# WallGrinder.net
KiCad netlist of a schematic drawn in EAGLE
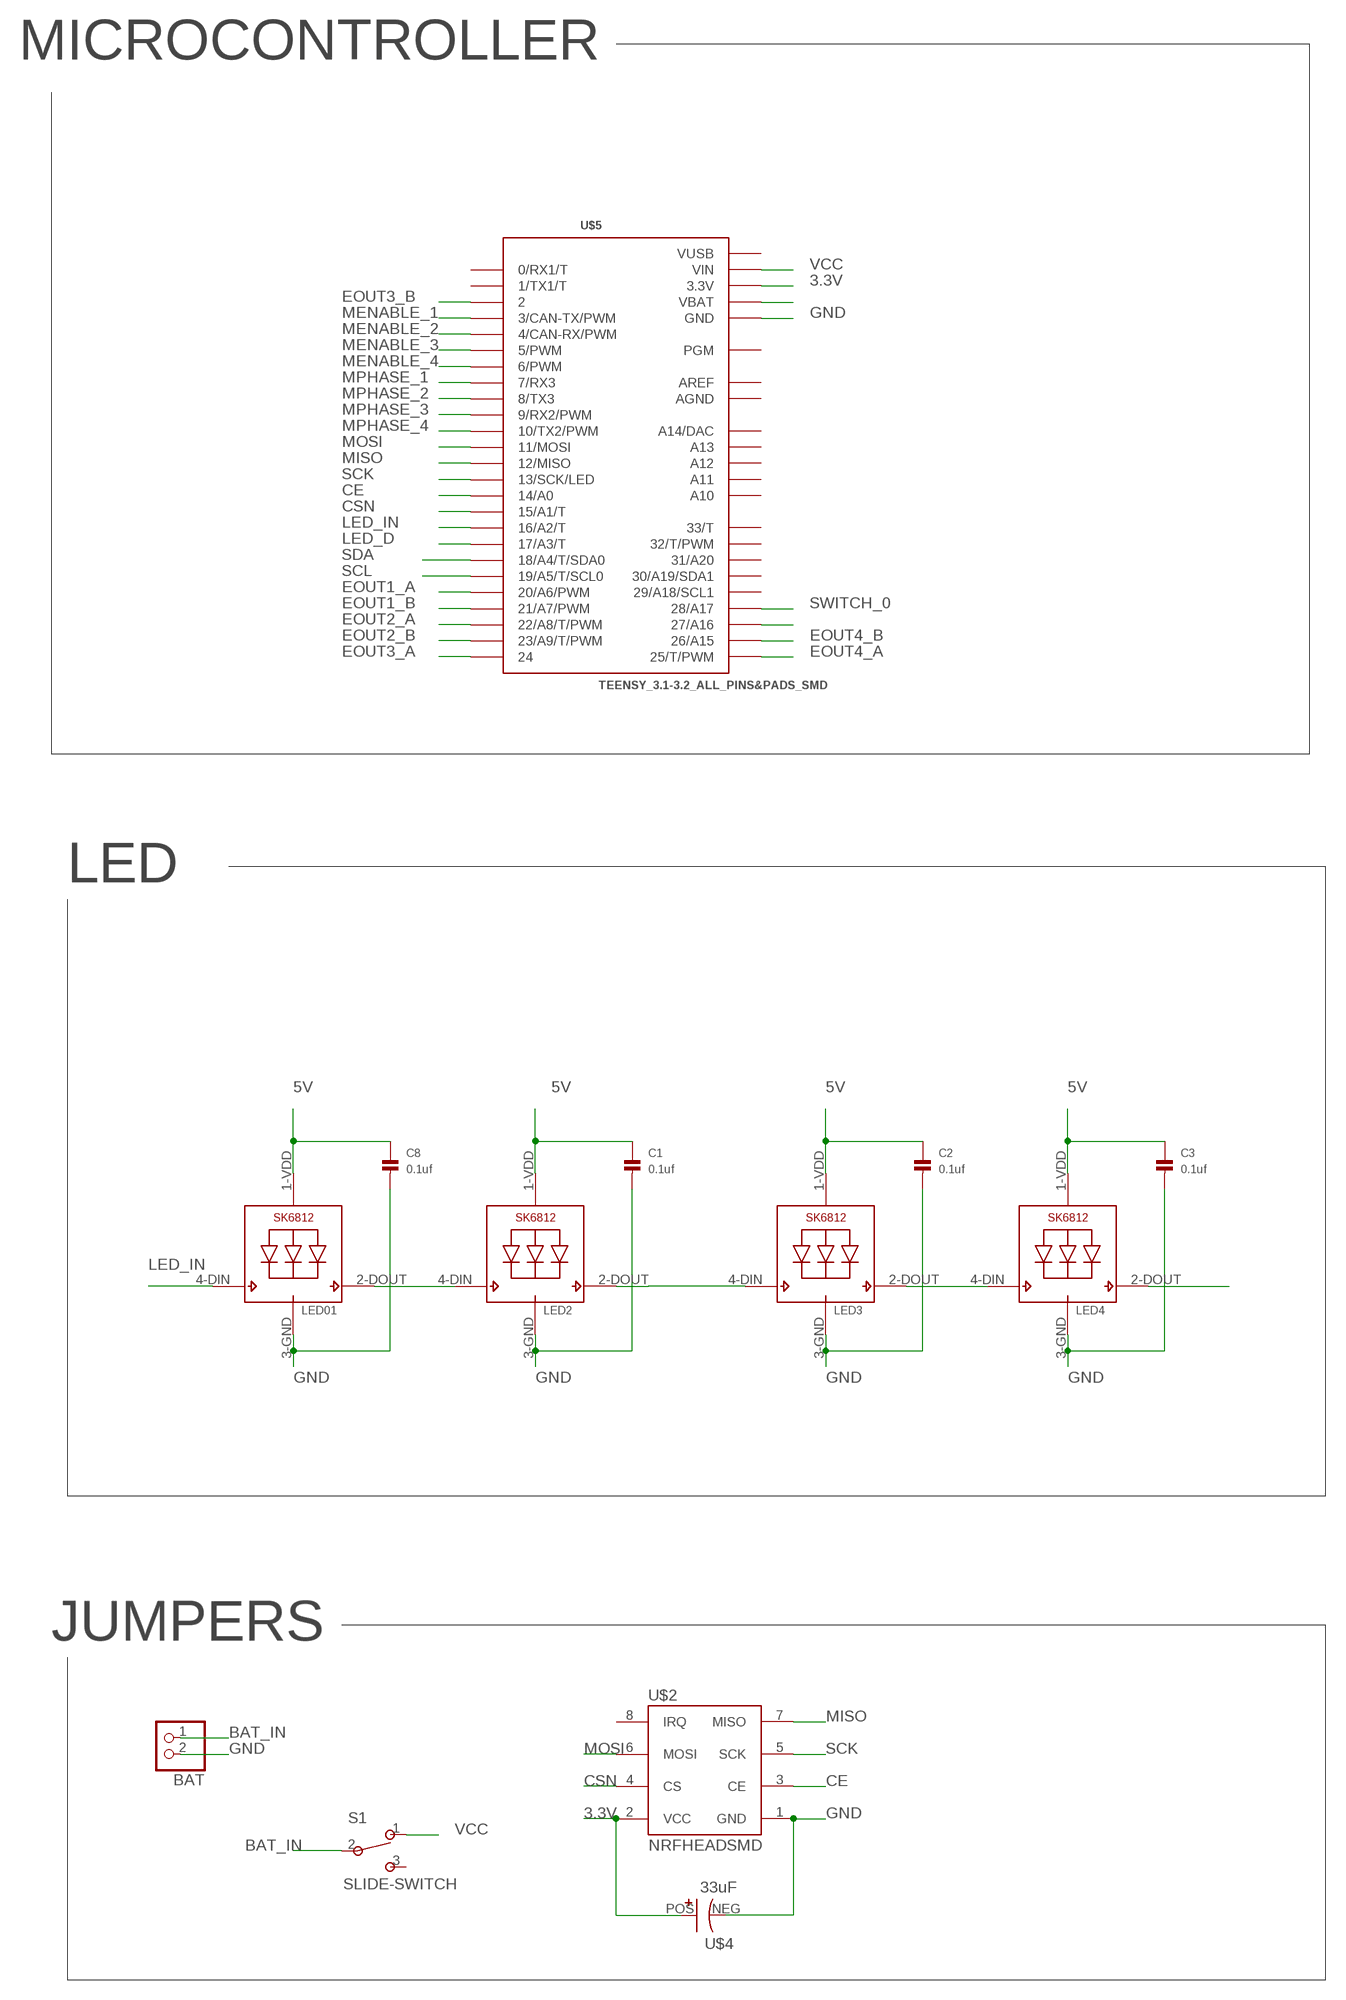
[diagram p0: schematic, sheet 1, part 1 of 2]
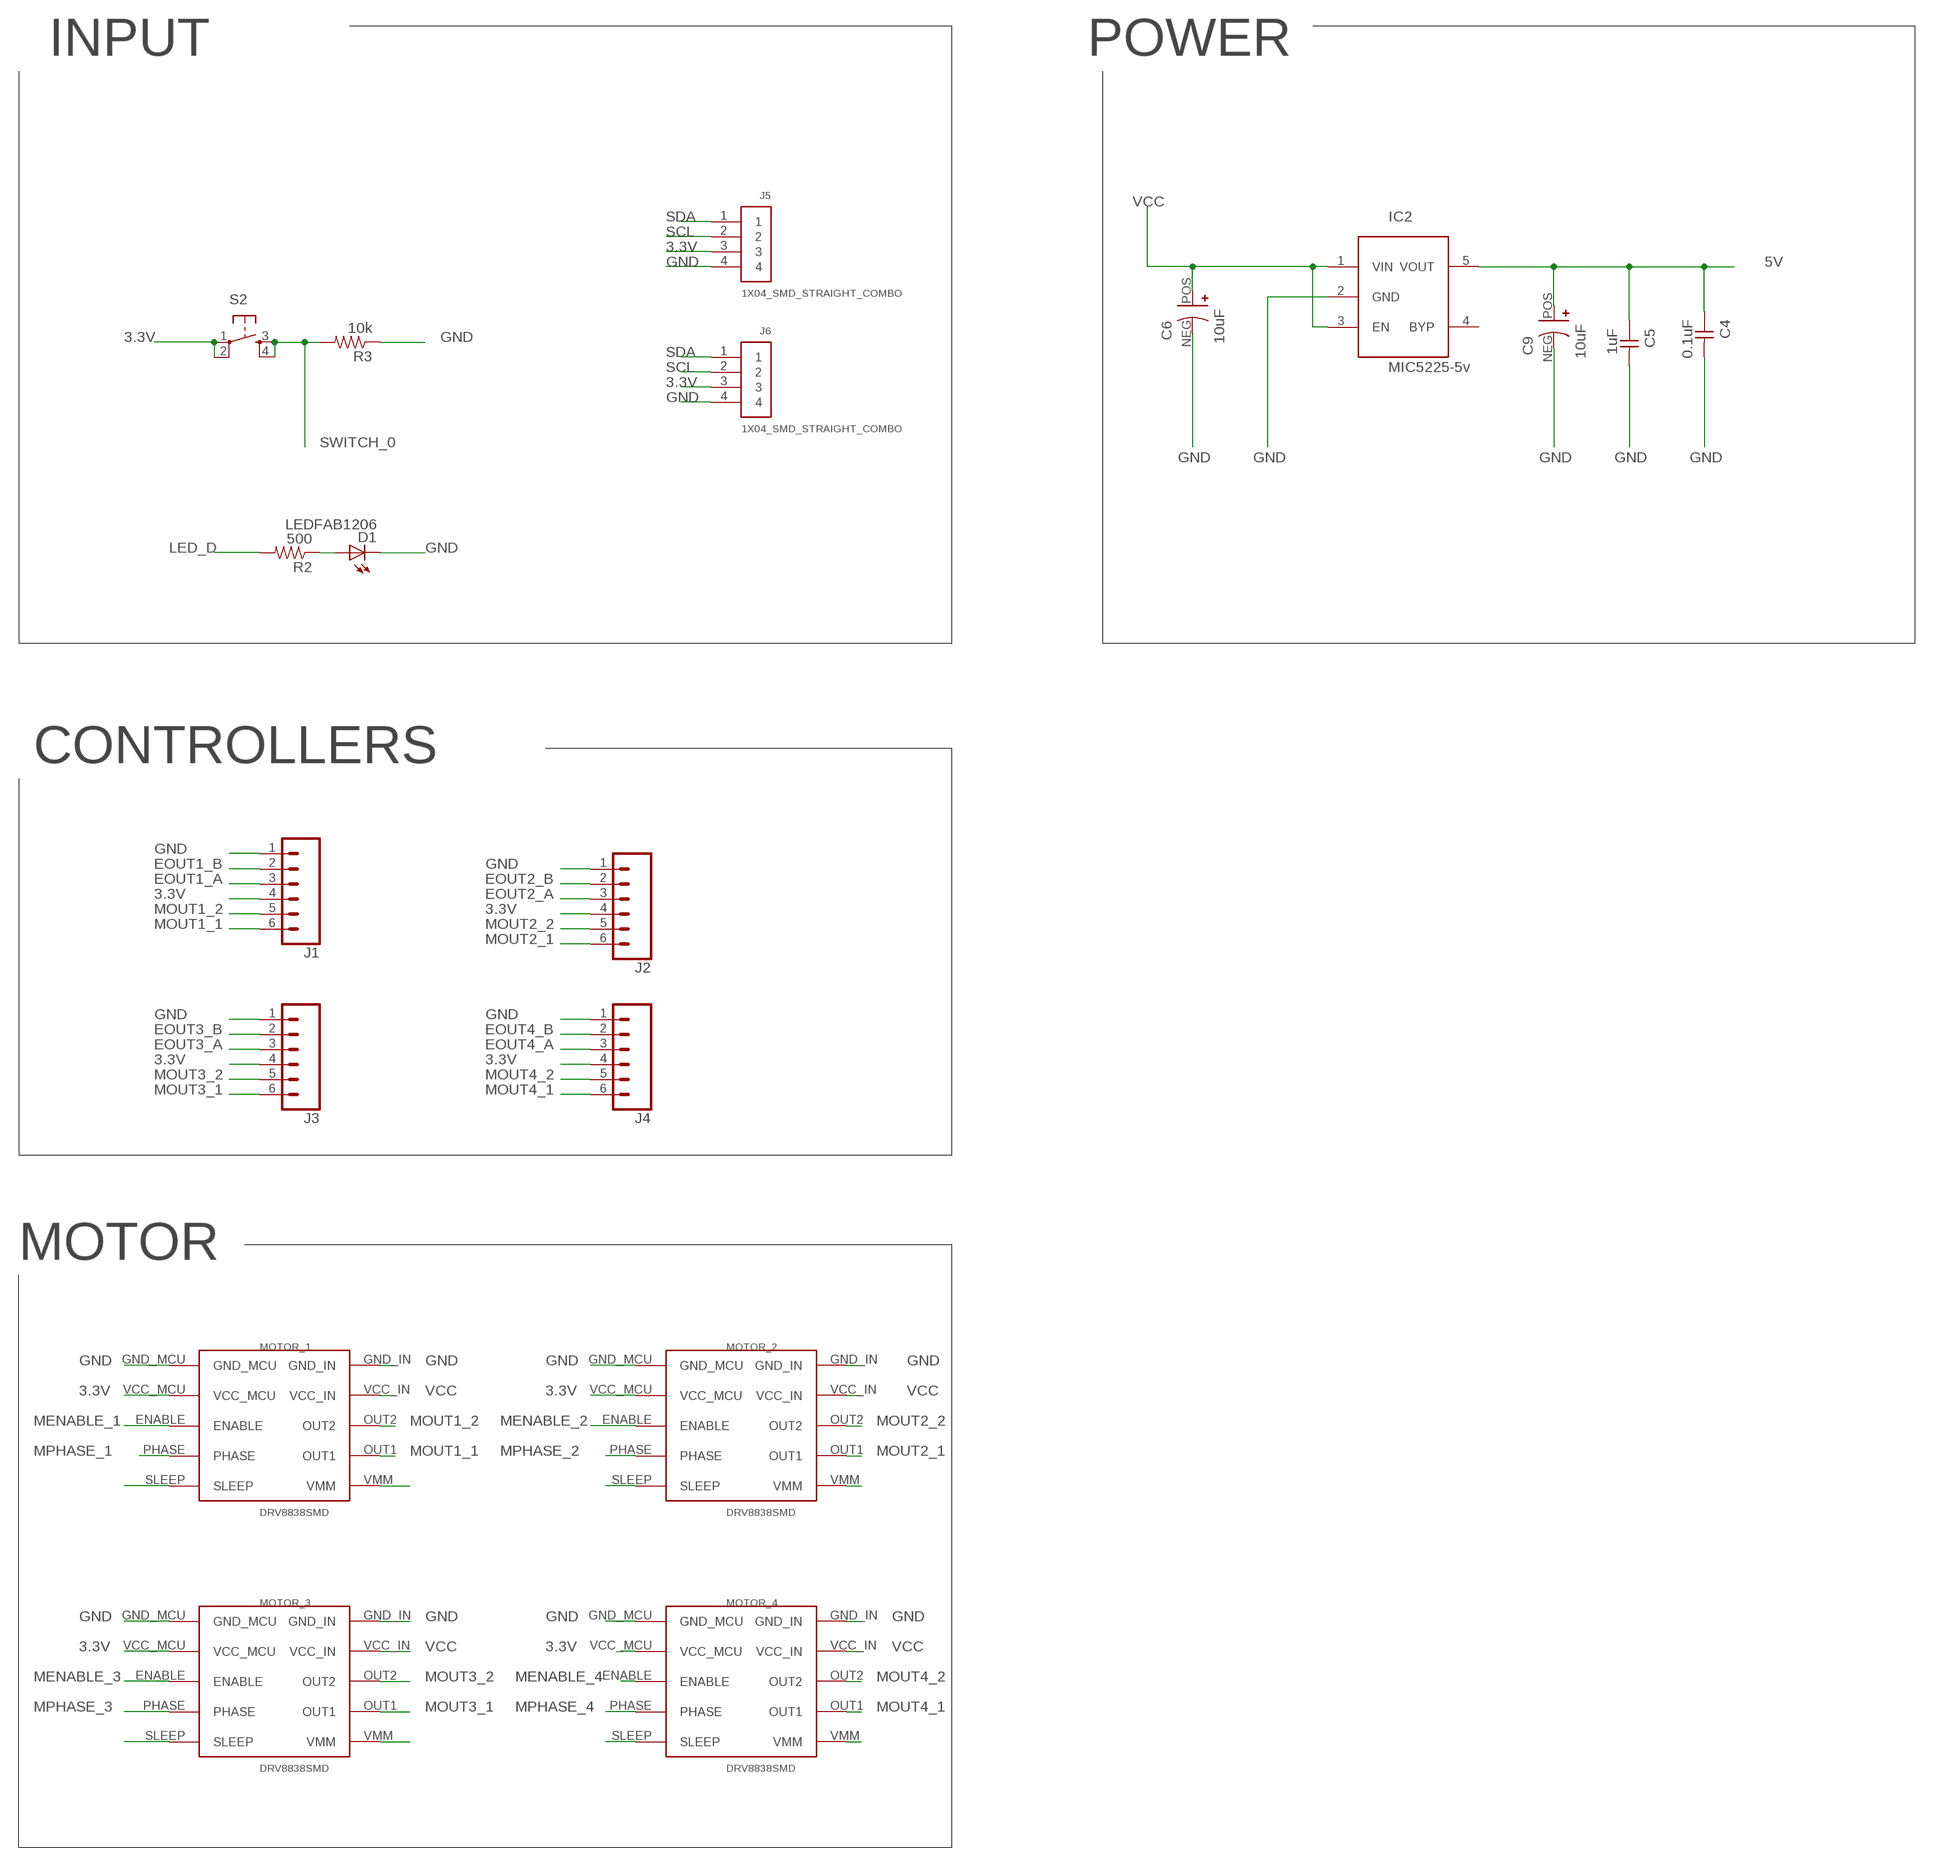
[diagram p1: schematic, sheet 1, part 2 of 2]

(export (version "E")
  (design (tool "Eeschema 10.0.6"))
  (components
    (comp (ref "BAT")
      (value "JST_2PIN-SMT-RA")
      (footprint "eagle-import:JST-PH-2-SMT-RA")
      (libsource (lib "eagle-import") (part "JST_2PIN-SMT-RA"))
    )
    (comp (ref "C1")
      (value "0.1uf")
      (footprint "eagle-import:1206")
      (libsource (lib "eagle-import") (part "CAP_CERAMIC1206"))
    )
    (comp (ref "C2")
      (value "0.1uf")
      (footprint "eagle-import:1206")
      (libsource (lib "eagle-import") (part "CAP_CERAMIC1206"))
    )
    (comp (ref "C3")
      (value "0.1uf")
      (footprint "eagle-import:1206")
      (libsource (lib "eagle-import") (part "CAP_CERAMIC1206"))
    )
    (comp (ref "C4")
      (value "0.1uF")
      (footprint "eagle-import:C1206FAB")
      (libsource (lib "eagle-import") (part "CAP-UNPOLARIZEDFAB"))
    )
    (comp (ref "C5")
      (value "1uF")
      (footprint "eagle-import:C1206FAB")
      (libsource (lib "eagle-import") (part "CAP-UNPOLARIZEDFAB"))
    )
    (comp (ref "C6")
      (value "10uF")
      (footprint "eagle-import:PANASONIC-CAP-SMD-B")
      (libsource (lib "eagle-import") (part "POLCAP-PANASONIC-SMD-B01"))
    )
    (comp (ref "C8")
      (value "0.1uf")
      (footprint "eagle-import:1206")
      (libsource (lib "eagle-import") (part "CAP_CERAMIC1206"))
    )
    (comp (ref "C9")
      (value "10uF")
      (footprint "eagle-import:PANASONIC-CAP-SMD-B")
      (libsource (lib "eagle-import") (part "POLCAP-PANASONIC-SMD-B01"))
    )
    (comp (ref "D1")
      (value "LEDFAB1206")
      (footprint "eagle-import:LED1206FAB")
      (libsource (lib "eagle-import") (part "LEDFAB1206"))
    )
    (comp (ref "IC2")
      (value "MIC5225-5v")
      (footprint "eagle-import:SOT23-5L")
      (libsource (lib "eagle-import") (part "LP298XS"))
    )
    (comp (ref "J1")
      (value "CONN_06SMD_MALE")
      (footprint "eagle-import:1X06_SMD_MALE")
      (fields (field (name "SPICEPREFIX") "X"))
      (libsource (lib "eagle-import") (part "CONN_06SMD_MALE"))
    )
    (comp (ref "J2")
      (value "CONN_06SMD_MALE")
      (footprint "eagle-import:1X06_SMD_MALE")
      (libsource (lib "eagle-import") (part "CONN_06SMD_MALE"))
    )
    (comp (ref "J3")
      (value "CONN_06SMD_MALE")
      (footprint "eagle-import:1X06_SMD_MALE")
      (libsource (lib "eagle-import") (part "CONN_06SMD_MALE"))
    )
    (comp (ref "J4")
      (value "CONN_06SMD_MALE")
      (footprint "eagle-import:1X06_SMD_MALE")
      (libsource (lib "eagle-import") (part "CONN_06SMD_MALE"))
    )
    (comp (ref "J5")
      (value "1X04_SMD_STRAIGHT_COMBO")
      (footprint "eagle-import:1X4-SMT")
      (libsource (lib "eagle-import") (part "1X4SMT"))
    )
    (comp (ref "J6")
      (value "1X04_SMD_STRAIGHT_COMBO")
      (footprint "eagle-import:1X4-SMT")
      (libsource (lib "eagle-import") (part "1X4SMT"))
    )
    (comp (ref "LED01")
      (value "SK6812_5050")
      (footprint "eagle-import:LED5050")
      (libsource (lib "eagle-import") (part "SK6812_5050"))
    )
    (comp (ref "LED2")
      (value "SK6812_5050")
      (footprint "eagle-import:LED5050")
      (libsource (lib "eagle-import") (part "SK6812_5050"))
    )
    (comp (ref "LED3")
      (value "SK6812_5050")
      (footprint "eagle-import:LED5050")
      (libsource (lib "eagle-import") (part "SK6812_5050"))
    )
    (comp (ref "LED4")
      (value "SK6812_5050")
      (footprint "eagle-import:LED5050")
      (libsource (lib "eagle-import") (part "SK6812_5050"))
    )
    (comp (ref "MOTOR_1")
      (value "DRV8838SMD")
      (footprint "eagle-import:DRV8838SMD")
      (libsource (lib "eagle-import") (part "DRV8838SMD"))
    )
    (comp (ref "MOTOR_2")
      (value "DRV8838SMD")
      (footprint "eagle-import:DRV8838SMD")
      (libsource (lib "eagle-import") (part "DRV8838SMD"))
    )
    (comp (ref "MOTOR_3")
      (value "DRV8838SMD")
      (footprint "eagle-import:DRV8838SMD")
      (libsource (lib "eagle-import") (part "DRV8838SMD"))
    )
    (comp (ref "MOTOR_4")
      (value "DRV8838SMD")
      (footprint "eagle-import:DRV8838SMD")
      (libsource (lib "eagle-import") (part "DRV8838SMD"))
    )
    (comp (ref "R2")
      (value "500")
      (footprint "eagle-import:R1206FAB")
      (libsource (lib "eagle-import") (part "RES-US1206FAB"))
    )
    (comp (ref "R3")
      (value "10k")
      (footprint "eagle-import:R1206FAB")
      (libsource (lib "eagle-import") (part "RES-US1206FAB"))
    )
    (comp (ref "S1")
      (value "SLIDE-SWITCH")
      (footprint "eagle-import:AYZ0102AGRLC")
      (libsource (lib "eagle-import") (part "SLIDE-SWITCH"))
    )
    (comp (ref "S2")
      (value "6MM_SWITCH6MM_SWITCH")
      (footprint "eagle-import:6MM_SWITCH")
      (libsource (lib "eagle-import") (part "6MM_SWITCH6MM_SWITCH"))
    )
    (comp (ref "U$2")
      (value "NRFHEADSMD")
      (footprint "eagle-import:2.54MM")
      (libsource (lib "eagle-import") (part "NRFHEADSMD"))
    )
    (comp (ref "U$4")
      (value "33uF")
      (footprint "eagle-import:PANASONIC-CAP-SMD-C")
      (libsource (lib "eagle-import") (part "POLCAP-PANASONIC-SMD-C"))
    )
    (comp (ref "U$5")
      (value "TEENSY_3.1-3.2_ALL_PINS&PADS_SMD")
      (footprint "eagle-import:TEENSY_3.0-3.2_ALL_PINS_&_PADS_SMD")
      (libsource (lib "eagle-import") (part "TEENSY_3.1-3.2_ALL_PINS&PADS_SMD"))
    )
  )
  (nets
    (net (code "1") (name "/3.3V") (class "Default")
      (node (ref "J1") (pin "4") (pinfunction "4_4") (pintype "passive"))
      (node (ref "J2") (pin "4") (pinfunction "4_4") (pintype "passive"))
      (node (ref "J3") (pin "4") (pinfunction "4_4") (pintype "passive"))
      (node (ref "J4") (pin "4") (pinfunction "4_4") (pintype "passive"))
      (node (ref "J5") (pin "3") (pinfunction "3_3") (pintype "bidirectional"))
      (node (ref "J6") (pin "3") (pinfunction "3_3") (pintype "bidirectional"))
      (node (ref "MOTOR_1") (pin "VCC_MCU") (pinfunction "VCC_MCU_VCC_MCU") (pintype "bidirectional"))
      (node (ref "MOTOR_2") (pin "VCC_MCU") (pinfunction "VCC_MCU_VCC_MCU") (pintype "bidirectional"))
      (node (ref "MOTOR_3") (pin "VCC_MCU") (pinfunction "VCC_MCU_VCC_MCU") (pintype "bidirectional"))
      (node (ref "MOTOR_4") (pin "VCC_MCU") (pinfunction "VCC_MCU_VCC_MCU") (pintype "bidirectional"))
      (node (ref "S2") (pin "1") (pinfunction "P_1") (pintype "passive"))
      (node (ref "S2") (pin "2") (pinfunction "P1_2") (pintype "passive"))
      (node (ref "U$2") (pin "2") (pinfunction "VCC_2") (pintype "bidirectional"))
      (node (ref "U$4") (pin "POS") (pinfunction "+_POS") (pintype "bidirectional"))
      (node (ref "U$5") (pin "3.3V") (pinfunction "3.3V_3.3V") (pintype "power_in"))
      (node (ref "U$5") (pin "3.3V1") (pinfunction "3.3V_3.3V1") (pintype "power_in"))
      (node (ref "U$5") (pin "3.3V2") (pinfunction "3.3V_3.3V2") (pintype "power_in"))
    )
    (net (code "2") (name "/5V") (class "Default")
      (node (ref "C1") (pin "1") (pinfunction "P$1_1") (pintype "passive"))
      (node (ref "C2") (pin "1") (pinfunction "P$1_1") (pintype "passive"))
      (node (ref "C3") (pin "1") (pinfunction "P$1_1") (pintype "passive"))
      (node (ref "C4") (pin "1") (pinfunction "1_1") (pintype "passive"))
      (node (ref "C5") (pin "1") (pinfunction "1_1") (pintype "passive"))
      (node (ref "C8") (pin "1") (pinfunction "P$1_1") (pintype "passive"))
      (node (ref "C9") (pin "POS") (pinfunction "+_POS") (pintype "bidirectional"))
      (node (ref "IC2") (pin "5") (pinfunction "VOUT_5") (pintype "bidirectional"))
      (node (ref "LED01") (pin "1-VDD") (pinfunction "VDD_1-VDD") (pintype "power_in"))
      (node (ref "LED2") (pin "1-VDD") (pinfunction "VDD_1-VDD") (pintype "power_in"))
      (node (ref "LED3") (pin "1-VDD") (pinfunction "VDD_1-VDD") (pintype "power_in"))
      (node (ref "LED4") (pin "1-VDD") (pinfunction "VDD_1-VDD") (pintype "power_in"))
    )
    (net (code "3") (name "/AGND") (class "Default")
      (node (ref "U$5") (pin "AGND") (pinfunction "AGND_AGND") (pintype "power_in"))
    )
    (net (code "4") (name "/AREF") (class "Default")
      (node (ref "U$5") (pin "AREF") (pinfunction "AREF_AREF") (pintype "power_in"))
    )
    (net (code "5") (name "/BAT_IN") (class "Default")
      (node (ref "BAT") (pin "1") (pinfunction "2_1") (pintype "passive"))
      (node (ref "S1") (pin "2") (pinfunction "2_2") (pintype "bidirectional"))
    )
    (net (code "6") (name "/CE") (class "Default")
      (node (ref "U$2") (pin "3") (pinfunction "CE_3") (pintype "bidirectional"))
      (node (ref "U$5") (pin "14/A0") (pinfunction "14/A0_14/A0") (pintype "bidirectional"))
    )
    (net (code "7") (name "/CSN") (class "Default")
      (node (ref "U$2") (pin "4") (pinfunction "CS_4") (pintype "bidirectional"))
      (node (ref "U$5") (pin "15/A1") (pinfunction "15/A1/T_15/A1") (pintype "bidirectional"))
    )
    (net (code "8") (name "/EOUT1_A") (class "Default")
      (node (ref "J1") (pin "3") (pinfunction "3_3") (pintype "passive"))
      (node (ref "U$5") (pin "20/A6") (pinfunction "20/A6/PWM_20/A6") (pintype "bidirectional"))
    )
    (net (code "9") (name "/EOUT1_B") (class "Default")
      (node (ref "J1") (pin "2") (pinfunction "2_2") (pintype "passive"))
      (node (ref "U$5") (pin "21/A7") (pinfunction "21/A7/PWM_21/A7") (pintype "bidirectional"))
    )
    (net (code "10") (name "/EOUT2_A") (class "Default")
      (node (ref "J2") (pin "3") (pinfunction "3_3") (pintype "passive"))
      (node (ref "U$5") (pin "22/A8") (pinfunction "22/A8/T/PWM_22/A8") (pintype "bidirectional"))
    )
    (net (code "11") (name "/EOUT2_B") (class "Default")
      (node (ref "J2") (pin "2") (pinfunction "2_2") (pintype "passive"))
      (node (ref "U$5") (pin "23/A9") (pinfunction "23/A9/T/PWM_23/A9") (pintype "bidirectional"))
    )
    (net (code "12") (name "/EOUT3_A") (class "Default")
      (node (ref "J3") (pin "3") (pinfunction "3_3") (pintype "passive"))
      (node (ref "U$5") (pin "24") (pinfunction "24_24") (pintype "bidirectional"))
    )
    (net (code "13") (name "/EOUT3_B") (class "Default")
      (node (ref "J3") (pin "2") (pinfunction "2_2") (pintype "passive"))
      (node (ref "U$5") (pin "2") (pinfunction "2_2") (pintype "bidirectional"))
    )
    (net (code "14") (name "/EOUT4_A") (class "Default")
      (node (ref "J4") (pin "3") (pinfunction "3_3") (pintype "passive"))
      (node (ref "U$5") (pin "25") (pinfunction "25/T/PWM_25") (pintype "bidirectional"))
    )
    (net (code "15") (name "/EOUT4_B") (class "Default")
      (node (ref "J4") (pin "2") (pinfunction "2_2") (pintype "passive"))
      (node (ref "U$5") (pin "26") (pinfunction "26/A15_26") (pintype "bidirectional"))
    )
    (net (code "16") (name "/GND") (class "Default")
      (node (ref "BAT") (pin "2") (pinfunction "1_2") (pintype "passive"))
      (node (ref "C1") (pin "2") (pinfunction "P$2_2") (pintype "passive"))
      (node (ref "C2") (pin "2") (pinfunction "P$2_2") (pintype "passive"))
      (node (ref "C3") (pin "2") (pinfunction "P$2_2") (pintype "passive"))
      (node (ref "C4") (pin "2") (pinfunction "2_2") (pintype "passive"))
      (node (ref "C5") (pin "2") (pinfunction "2_2") (pintype "passive"))
      (node (ref "C6") (pin "NEG") (pinfunction "-_NEG") (pintype "bidirectional"))
      (node (ref "C8") (pin "2") (pinfunction "P$2_2") (pintype "passive"))
      (node (ref "C9") (pin "NEG") (pinfunction "-_NEG") (pintype "bidirectional"))
      (node (ref "D1") (pin "2") (pinfunction "C_2") (pintype "passive"))
      (node (ref "IC2") (pin "2") (pinfunction "GND_2") (pintype "bidirectional"))
      (node (ref "J1") (pin "1") (pinfunction "1_1") (pintype "passive"))
      (node (ref "J2") (pin "1") (pinfunction "1_1") (pintype "passive"))
      (node (ref "J3") (pin "1") (pinfunction "1_1") (pintype "passive"))
      (node (ref "J4") (pin "1") (pinfunction "1_1") (pintype "passive"))
      (node (ref "J5") (pin "4") (pinfunction "4_4") (pintype "bidirectional"))
      (node (ref "J6") (pin "4") (pinfunction "4_4") (pintype "bidirectional"))
      (node (ref "LED01") (pin "3-GND") (pinfunction "GND_3-GND") (pintype "power_in"))
      (node (ref "LED2") (pin "3-GND") (pinfunction "GND_3-GND") (pintype "power_in"))
      (node (ref "LED3") (pin "3-GND") (pinfunction "GND_3-GND") (pintype "power_in"))
      (node (ref "LED4") (pin "3-GND") (pinfunction "GND_3-GND") (pintype "power_in"))
      (node (ref "MOTOR_1") (pin "GND_IN") (pinfunction "GND_IN_GND_IN") (pintype "bidirectional"))
      (node (ref "MOTOR_1") (pin "GND_MCU") (pinfunction "GND_MCU_GND_MCU") (pintype "bidirectional"))
      (node (ref "MOTOR_2") (pin "GND_IN") (pinfunction "GND_IN_GND_IN") (pintype "bidirectional"))
      (node (ref "MOTOR_2") (pin "GND_MCU") (pinfunction "GND_MCU_GND_MCU") (pintype "bidirectional"))
      (node (ref "MOTOR_3") (pin "GND_IN") (pinfunction "GND_IN_GND_IN") (pintype "bidirectional"))
      (node (ref "MOTOR_3") (pin "GND_MCU") (pinfunction "GND_MCU_GND_MCU") (pintype "bidirectional"))
      (node (ref "MOTOR_4") (pin "GND_IN") (pinfunction "GND_IN_GND_IN") (pintype "bidirectional"))
      (node (ref "MOTOR_4") (pin "GND_MCU") (pinfunction "GND_MCU_GND_MCU") (pintype "bidirectional"))
      (node (ref "R3") (pin "1") (pinfunction "1_1") (pintype "passive"))
      (node (ref "U$2") (pin "1") (pinfunction "GND_1") (pintype "bidirectional"))
      (node (ref "U$4") (pin "NEG") (pinfunction "-_NEG") (pintype "bidirectional"))
      (node (ref "U$5") (pin "GND") (pinfunction "GND_GND") (pintype "power_in"))
      (node (ref "U$5") (pin "GND1") (pinfunction "GND_GND1") (pintype "power_in"))
      (node (ref "U$5") (pin "GND2") (pinfunction "GND_GND2") (pintype "power_in"))
    )
    (net (code "17") (name "/LED_D") (class "Default")
      (node (ref "R2") (pin "2") (pinfunction "2_2") (pintype "passive"))
      (node (ref "U$5") (pin "17/A3") (pinfunction "17/A3/T_17/A3") (pintype "bidirectional"))
    )
    (net (code "18") (name "/LED_IN") (class "Default")
      (node (ref "LED01") (pin "4-DIN") (pinfunction "DI_4-DIN") (pintype "input"))
      (node (ref "U$5") (pin "16/A2") (pinfunction "16/A2/T_16/A2") (pintype "bidirectional"))
    )
    (net (code "19") (name "/MENABLE_1") (class "Default")
      (node (ref "MOTOR_1") (pin "ENABLE") (pinfunction "ENABLE_ENABLE") (pintype "bidirectional"))
      (node (ref "U$5") (pin "3") (pinfunction "3/CAN-TX/PWM_3") (pintype "bidirectional"))
    )
    (net (code "20") (name "/MENABLE_2") (class "Default")
      (node (ref "MOTOR_2") (pin "ENABLE") (pinfunction "ENABLE_ENABLE") (pintype "bidirectional"))
      (node (ref "U$5") (pin "4") (pinfunction "4/CAN-RX/PWM_4") (pintype "bidirectional"))
    )
    (net (code "21") (name "/MENABLE_3") (class "Default")
      (node (ref "MOTOR_3") (pin "ENABLE") (pinfunction "ENABLE_ENABLE") (pintype "bidirectional"))
      (node (ref "U$5") (pin "5") (pinfunction "5/PWM_5") (pintype "bidirectional"))
    )
    (net (code "22") (name "/MENABLE_4") (class "Default")
      (node (ref "MOTOR_4") (pin "ENABLE") (pinfunction "ENABLE_ENABLE") (pintype "bidirectional"))
      (node (ref "U$5") (pin "6") (pinfunction "6/PWM_6") (pintype "bidirectional"))
    )
    (net (code "23") (name "/MISO") (class "Default")
      (node (ref "U$2") (pin "7") (pinfunction "MISO_7") (pintype "bidirectional"))
      (node (ref "U$5") (pin "12") (pinfunction "12/MISO_12") (pintype "bidirectional"))
    )
    (net (code "24") (name "/MOSI") (class "Default")
      (node (ref "U$2") (pin "6") (pinfunction "MOSI_6") (pintype "bidirectional"))
      (node (ref "U$5") (pin "11") (pinfunction "11/MOSI_11") (pintype "bidirectional"))
    )
    (net (code "25") (name "/MOUT1_1") (class "Default")
      (node (ref "J1") (pin "6") (pinfunction "6_6") (pintype "passive"))
      (node (ref "MOTOR_1") (pin "OUT1") (pinfunction "OUT1_OUT1") (pintype "bidirectional"))
    )
    (net (code "26") (name "/MOUT1_2") (class "Default")
      (node (ref "J1") (pin "5") (pinfunction "5_5") (pintype "passive"))
      (node (ref "MOTOR_1") (pin "OUT2") (pinfunction "OUT2_OUT2") (pintype "bidirectional"))
    )
    (net (code "27") (name "/MOUT2_1") (class "Default")
      (node (ref "J2") (pin "6") (pinfunction "6_6") (pintype "passive"))
      (node (ref "MOTOR_2") (pin "OUT1") (pinfunction "OUT1_OUT1") (pintype "bidirectional"))
    )
    (net (code "28") (name "/MOUT2_2") (class "Default")
      (node (ref "J2") (pin "5") (pinfunction "5_5") (pintype "passive"))
      (node (ref "MOTOR_2") (pin "OUT2") (pinfunction "OUT2_OUT2") (pintype "bidirectional"))
    )
    (net (code "29") (name "/MOUT3_1") (class "Default")
      (node (ref "J3") (pin "6") (pinfunction "6_6") (pintype "passive"))
      (node (ref "MOTOR_3") (pin "OUT1") (pinfunction "OUT1_OUT1") (pintype "bidirectional"))
    )
    (net (code "30") (name "/MOUT3_2") (class "Default")
      (node (ref "J3") (pin "5") (pinfunction "5_5") (pintype "passive"))
      (node (ref "MOTOR_3") (pin "OUT2") (pinfunction "OUT2_OUT2") (pintype "bidirectional"))
    )
    (net (code "31") (name "/MOUT4_1") (class "Default")
      (node (ref "J4") (pin "6") (pinfunction "6_6") (pintype "passive"))
      (node (ref "MOTOR_4") (pin "OUT1") (pinfunction "OUT1_OUT1") (pintype "bidirectional"))
    )
    (net (code "32") (name "/MOUT4_2") (class "Default")
      (node (ref "J4") (pin "5") (pinfunction "5_5") (pintype "passive"))
      (node (ref "MOTOR_4") (pin "OUT2") (pinfunction "OUT2_OUT2") (pintype "bidirectional"))
    )
    (net (code "33") (name "/MPHASE_1") (class "Default")
      (node (ref "MOTOR_1") (pin "PHASE") (pinfunction "PHASE_PHASE") (pintype "bidirectional"))
      (node (ref "U$5") (pin "7") (pinfunction "7/RX3_7") (pintype "bidirectional"))
    )
    (net (code "34") (name "/MPHASE_2") (class "Default")
      (node (ref "MOTOR_2") (pin "PHASE") (pinfunction "PHASE_PHASE") (pintype "bidirectional"))
      (node (ref "U$5") (pin "8") (pinfunction "8/TX3_8") (pintype "bidirectional"))
    )
    (net (code "35") (name "/MPHASE_3") (class "Default")
      (node (ref "MOTOR_3") (pin "PHASE") (pinfunction "PHASE_PHASE") (pintype "bidirectional"))
      (node (ref "U$5") (pin "9") (pinfunction "9/RX2/PWM_9") (pintype "bidirectional"))
    )
    (net (code "36") (name "/MPHASE_4") (class "Default")
      (node (ref "MOTOR_4") (pin "PHASE") (pinfunction "PHASE_PHASE") (pintype "bidirectional"))
      (node (ref "U$5") (pin "10") (pinfunction "10/TX2/PWM_10") (pintype "bidirectional"))
    )
    (net (code "37") (name "/SCK") (class "Default")
      (node (ref "U$2") (pin "5") (pinfunction "SCK_5") (pintype "bidirectional"))
      (node (ref "U$5") (pin "13") (pinfunction "13/SCK/LED_13") (pintype "bidirectional"))
    )
    (net (code "38") (name "/SCL") (class "Default")
      (node (ref "J5") (pin "2") (pinfunction "2_2") (pintype "bidirectional"))
      (node (ref "J6") (pin "2") (pinfunction "2_2") (pintype "bidirectional"))
      (node (ref "U$5") (pin "19/A5") (pinfunction "19/A5/T/SCL0_19/A5") (pintype "bidirectional"))
    )
    (net (code "39") (name "/SDA") (class "Default")
      (node (ref "J5") (pin "1") (pinfunction "1_1") (pintype "bidirectional"))
      (node (ref "J6") (pin "1") (pinfunction "1_1") (pintype "bidirectional"))
      (node (ref "U$5") (pin "18/A4") (pinfunction "18/A4/T/SDA0_18/A4") (pintype "bidirectional"))
    )
    (net (code "40") (name "/SWITCH_0") (class "Default")
      (node (ref "R3") (pin "2") (pinfunction "2_2") (pintype "passive"))
      (node (ref "S2") (pin "3") (pinfunction "S_3") (pintype "passive"))
      (node (ref "S2") (pin "4") (pinfunction "S1_4") (pintype "passive"))
      (node (ref "U$5") (pin "28") (pinfunction "28/A17_28") (pintype "bidirectional"))
    )
    (net (code "41") (name "/VCC") (class "Default")
      (node (ref "C6") (pin "POS") (pinfunction "+_POS") (pintype "bidirectional"))
      (node (ref "IC2") (pin "1") (pinfunction "VIN_1") (pintype "bidirectional"))
      (node (ref "IC2") (pin "3") (pinfunction "EN_3") (pintype "bidirectional"))
      (node (ref "MOTOR_1") (pin "VCC_IN") (pinfunction "VCC_IN_VCC_IN") (pintype "bidirectional"))
      (node (ref "MOTOR_2") (pin "VCC_IN") (pinfunction "VCC_IN_VCC_IN") (pintype "bidirectional"))
      (node (ref "MOTOR_3") (pin "VCC_IN") (pinfunction "VCC_IN_VCC_IN") (pintype "bidirectional"))
      (node (ref "MOTOR_4") (pin "VCC_IN") (pinfunction "VCC_IN_VCC_IN") (pintype "bidirectional"))
      (node (ref "S1") (pin "1") (pinfunction "1_1") (pintype "bidirectional"))
      (node (ref "U$5") (pin "VIN") (pinfunction "VIN_VIN") (pintype "power_in"))
    )
    (net (code "42") (name "/VUSB") (class "Default")
      (node (ref "U$5") (pin "VUSB") (pinfunction "VUSB_VUSB") (pintype "power_in"))
    )
    (net (code "43") (name "Net-(D1-A)") (class "Default")
      (node (ref "D1") (pin "1") (pinfunction "A_1") (pintype "passive"))
      (node (ref "R2") (pin "1") (pinfunction "1_1") (pintype "passive"))
    )
    (net (code "44") (name "Net-(LED01-DO)") (class "Default")
      (node (ref "LED01") (pin "2-DOUT") (pinfunction "DO_2-DOUT") (pintype "output"))
      (node (ref "LED2") (pin "4-DIN") (pinfunction "DI_4-DIN") (pintype "input"))
    )
    (net (code "45") (name "Net-(LED2-DO)") (class "Default")
      (node (ref "LED2") (pin "2-DOUT") (pinfunction "DO_2-DOUT") (pintype "output"))
      (node (ref "LED3") (pin "4-DIN") (pinfunction "DI_4-DIN") (pintype "input"))
    )
    (net (code "46") (name "Net-(LED3-DO)") (class "Default")
      (node (ref "LED3") (pin "2-DOUT") (pinfunction "DO_2-DOUT") (pintype "output"))
      (node (ref "LED4") (pin "4-DIN") (pinfunction "DI_4-DIN") (pintype "input"))
    )
    (net (code "47") (name "unconnected-(IC2-BYP-Pad4)") (class "Default")
      (node (ref "IC2") (pin "4") (pinfunction "BYP_4") (pintype "bidirectional"))
    )
    (net (code "48") (name "unconnected-(LED4-DO-Pad2-DOUT)") (class "Default")
      (node (ref "LED4") (pin "2-DOUT") (pinfunction "DO_2-DOUT") (pintype "output"))
    )
    (net (code "49") (name "unconnected-(MOTOR_1-PadSLEEP)") (class "Default")
      (node (ref "MOTOR_1") (pin "SLEEP") (pinfunction "SLEEP_SLEEP") (pintype "bidirectional"))
    )
    (net (code "50") (name "unconnected-(MOTOR_1-PadVMM)") (class "Default")
      (node (ref "MOTOR_1") (pin "VMM") (pinfunction "VMM_VMM") (pintype "bidirectional"))
    )
    (net (code "51") (name "unconnected-(MOTOR_2-PadSLEEP)") (class "Default")
      (node (ref "MOTOR_2") (pin "SLEEP") (pinfunction "SLEEP_SLEEP") (pintype "bidirectional"))
    )
    (net (code "52") (name "unconnected-(MOTOR_2-PadVMM)") (class "Default")
      (node (ref "MOTOR_2") (pin "VMM") (pinfunction "VMM_VMM") (pintype "bidirectional"))
    )
    (net (code "53") (name "unconnected-(MOTOR_3-PadSLEEP)") (class "Default")
      (node (ref "MOTOR_3") (pin "SLEEP") (pinfunction "SLEEP_SLEEP") (pintype "bidirectional"))
    )
    (net (code "54") (name "unconnected-(MOTOR_3-PadVMM)") (class "Default")
      (node (ref "MOTOR_3") (pin "VMM") (pinfunction "VMM_VMM") (pintype "bidirectional"))
    )
    (net (code "55") (name "unconnected-(MOTOR_4-PadSLEEP)") (class "Default")
      (node (ref "MOTOR_4") (pin "SLEEP") (pinfunction "SLEEP_SLEEP") (pintype "bidirectional"))
    )
    (net (code "56") (name "unconnected-(MOTOR_4-PadVMM)") (class "Default")
      (node (ref "MOTOR_4") (pin "VMM") (pinfunction "VMM_VMM") (pintype "bidirectional"))
    )
    (net (code "57") (name "unconnected-(S1-Pad3)") (class "Default")
      (node (ref "S1") (pin "3") (pinfunction "3_3") (pintype "bidirectional"))
    )
    (net (code "58") (name "unconnected-(U$2-IRQ-Pad8)") (class "Default")
      (node (ref "U$2") (pin "8") (pinfunction "IRQ_8") (pintype "bidirectional"))
    )
    (net (code "59") (name "unconnected-(U$5-0{slash}RX1{slash}T-Pad0)") (class "Default")
      (node (ref "U$5") (pin "0") (pinfunction "0/RX1/T_0") (pintype "bidirectional"))
    )
    (net (code "60") (name "unconnected-(U$5-1{slash}TX1{slash}T-Pad1)") (class "Default")
      (node (ref "U$5") (pin "1") (pinfunction "1/TX1/T_1") (pintype "bidirectional"))
    )
    (net (code "61") (name "unconnected-(U$5-27{slash}A16-Pad27)") (class "Default")
      (node (ref "U$5") (pin "27") (pinfunction "27/A16_27") (pintype "bidirectional"))
    )
    (net (code "62") (name "unconnected-(U$5-29{slash}A18{slash}SCL1-Pad29)") (class "Default")
      (node (ref "U$5") (pin "29") (pinfunction "29/A18/SCL1_29") (pintype "bidirectional"))
    )
    (net (code "63") (name "unconnected-(U$5-30{slash}A19{slash}SDA1-Pad30)") (class "Default")
      (node (ref "U$5") (pin "30") (pinfunction "30/A19/SDA1_30") (pintype "bidirectional"))
    )
    (net (code "64") (name "unconnected-(U$5-31{slash}A20-Pad31)") (class "Default")
      (node (ref "U$5") (pin "31") (pinfunction "31/A20_31") (pintype "bidirectional"))
    )
    (net (code "65") (name "unconnected-(U$5-32{slash}T{slash}PWM-Pad32)") (class "Default")
      (node (ref "U$5") (pin "32") (pinfunction "32/T/PWM_32") (pintype "bidirectional"))
    )
    (net (code "66") (name "unconnected-(U$5-33{slash}T-Pad33)") (class "Default")
      (node (ref "U$5") (pin "33") (pinfunction "33/T_33") (pintype "bidirectional"))
    )
    (net (code "67") (name "unconnected-(U$5-A14{slash}DAC-PadRESET{slash}DAC)") (class "Default")
      (node (ref "U$5") (pin "RESET/DAC") (pinfunction "A14/DAC_RESET/DAC") (pintype "bidirectional"))
    )
    (net (code "68") (name "unconnected-(U$5-PadA10)") (class "Default")
      (node (ref "U$5") (pin "A10") (pinfunction "A10_A10") (pintype "bidirectional"))
    )
    (net (code "69") (name "unconnected-(U$5-PadA11)") (class "Default")
      (node (ref "U$5") (pin "A11") (pinfunction "A11_A11") (pintype "bidirectional"))
    )
    (net (code "70") (name "unconnected-(U$5-PadA12)") (class "Default")
      (node (ref "U$5") (pin "A12") (pinfunction "A12_A12") (pintype "bidirectional"))
    )
    (net (code "71") (name "unconnected-(U$5-PadA13)") (class "Default")
      (node (ref "U$5") (pin "A13") (pinfunction "A13_A13") (pintype "bidirectional"))
    )
    (net (code "72") (name "unconnected-(U$5-PadPGM)") (class "Default")
      (node (ref "U$5") (pin "PGM") (pinfunction "PGM_PGM") (pintype "bidirectional"))
    )
    (net (code "73") (name "unconnected-(U$5-PadVBAT)") (class "Default")
      (node (ref "U$5") (pin "VBAT") (pinfunction "VBAT_VBAT") (pintype "power_in"))
    )
  )
)
